# ict_v361-xs-180.net
KiCad netlist of a schematic drawn in EAGLE
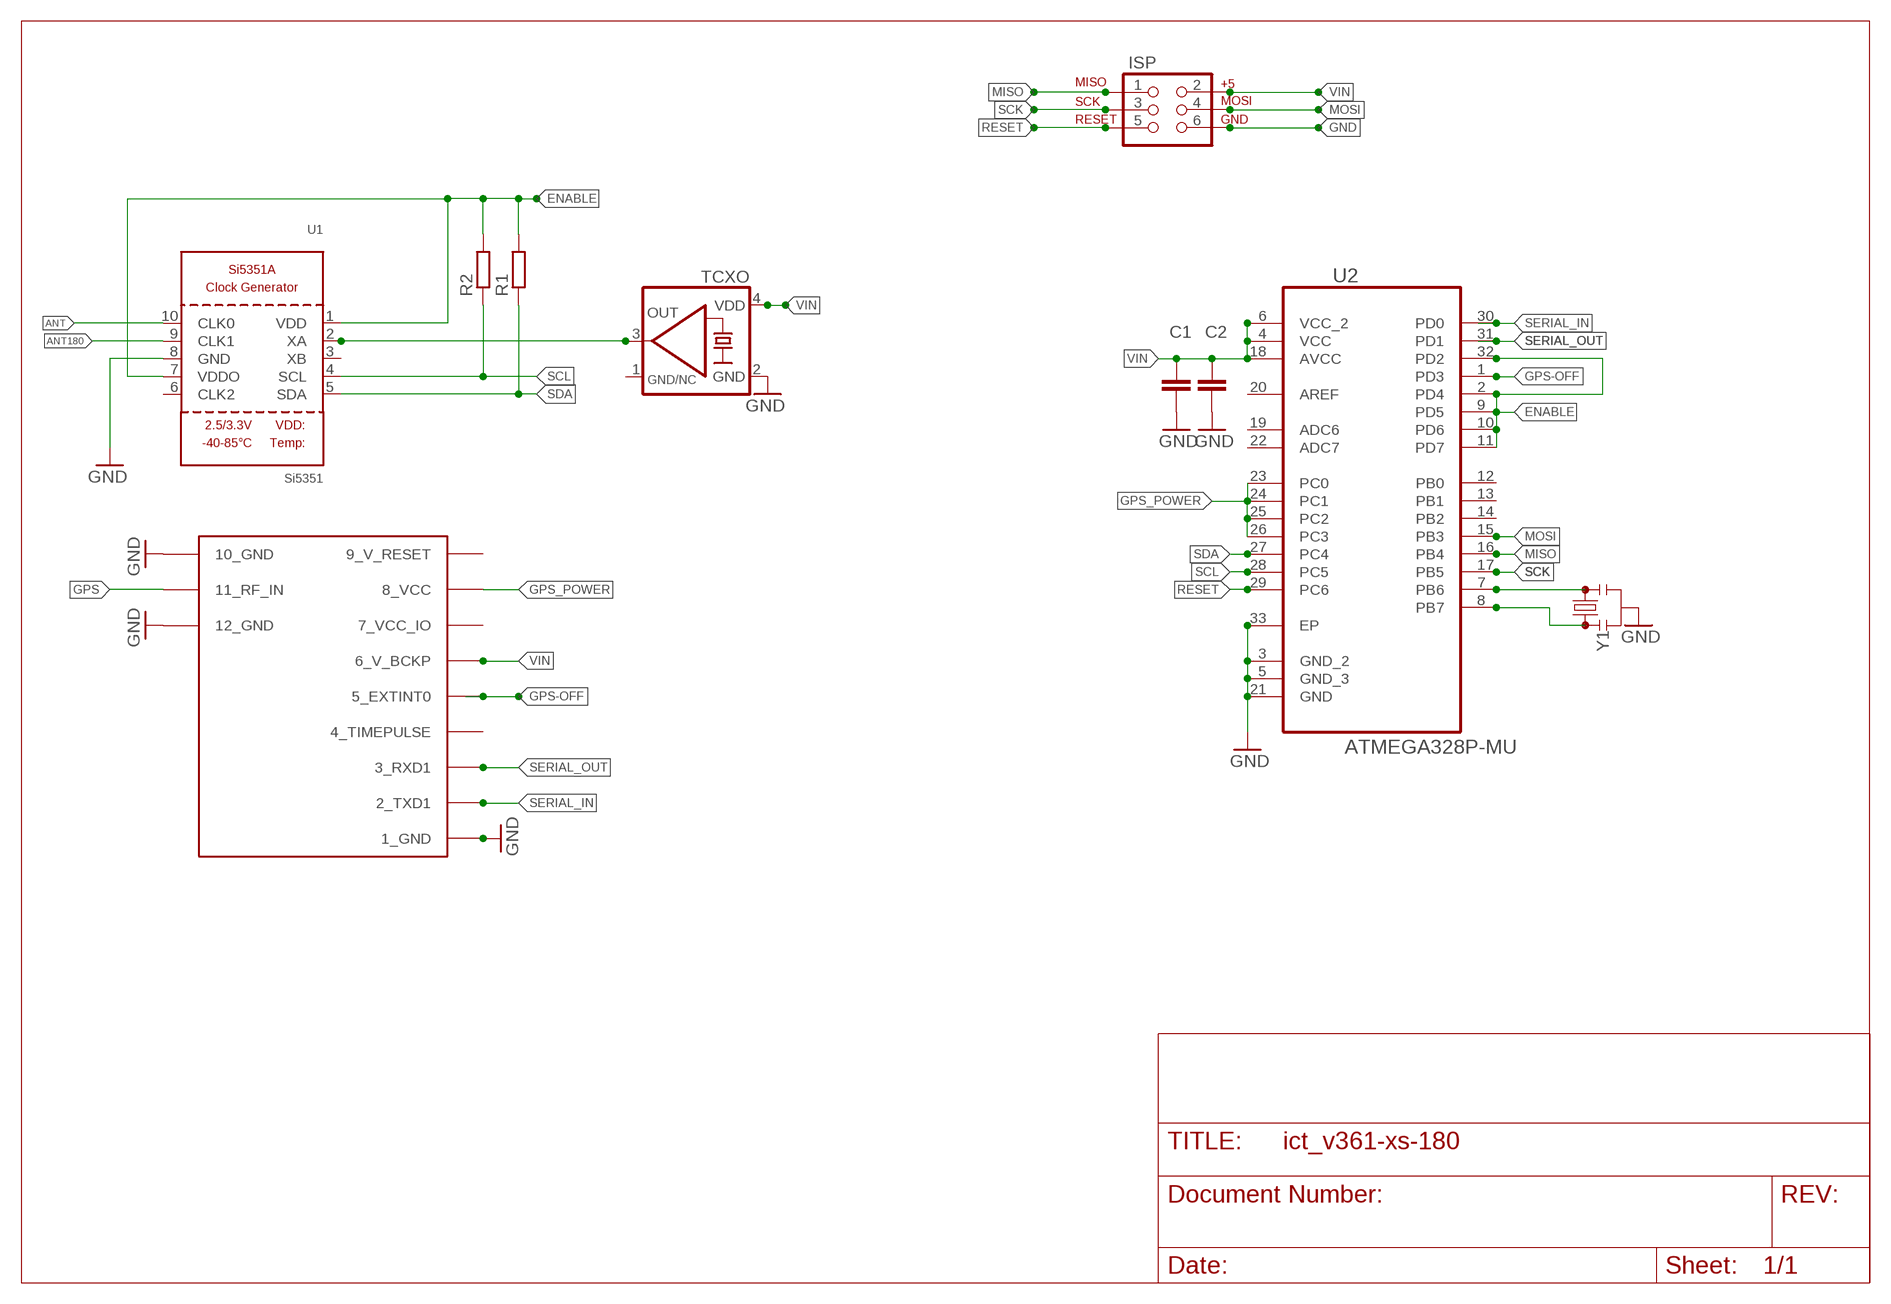
[diagram p0: schematic, sheet 1]

(export (version "E")
  (design (tool "Eeschema 10.0.6"))
  (components
    (comp (ref "C1")
      (value "C-EUC0603K")
      (footprint "eagle-import:C0603K")
      (libsource (lib "eagle-import") (part "C-EUC0603K"))
    )
    (comp (ref "C2")
      (value "C-EUC0603K")
      (footprint "eagle-import:C0603K")
      (libsource (lib "eagle-import") (part "C-EUC0603K"))
    )
    (comp (ref "GPS")
      (value "UBLOX_MAX")
      (footprint "eagle-import:UBLOX_MAX")
      (libsource (lib "eagle-import") (part "UBLOX_MAX"))
    )
    (comp (ref "ISP")
      (value "AVR_SPI_PRG_6PTH")
      (footprint "eagle-import:2X3")
      (libsource (lib "eagle-import") (part "AVR_SPI_PRG_6PTH"))
    )
    (comp (ref "R1")
      (value "R-EU_R0603")
      (footprint "eagle-import:R0603")
      (libsource (lib "eagle-import") (part "R-EU_R0603"))
    )
    (comp (ref "R2")
      (value "R-EU_R0603")
      (footprint "eagle-import:R0603")
      (libsource (lib "eagle-import") (part "R-EU_R0603"))
    )
    (comp (ref "TCXO")
      (value "KXO-TCXO-CMOS-84")
      (footprint "eagle-import:3.2X2.5_KXO-84-TCXO")
      (libsource (lib "eagle-import") (part "KXO-TCXO-CMOS-84"))
    )
    (comp (ref "U1")
      (value "Si5351")
      (footprint "eagle-import:MSOP10")
      (libsource (lib "eagle-import") (part "SI5351A"))
    )
    (comp (ref "U2")
      (value "ATMEGA328P-MU")
      (footprint "eagle-import:QFN50P500X500X100-33N")
      (libsource (lib "eagle-import") (part "ATMEGA328P-MU"))
    )
    (comp (ref "Y1")
      (value "RESONATORSMD-4.5X2.0")
      (footprint "eagle-import:RESONATOR-SMD-4.5X2.0")
      (libsource (lib "eagle-import") (part "RESONATORSMD-4.5X2.0"))
    )
  )
  (nets
    (net (code "1") (name "/7_VCC_IO") (class "Default")
      (node (ref "GPS") (pin "7_VCC_IO") (pinfunction "7_VCC_IO_7_VCC_IO") (pintype "power_in"))
    )
    (net (code "2") (name "/9_V_RESET") (class "Default")
      (node (ref "GPS") (pin "9_V_RESET") (pinfunction "9_V_RESET_9_V_RESET") (pintype "power_in"))
    )
    (net (code "3") (name "/GND{slash}NC") (class "Default")
      (node (ref "TCXO") (pin "1") (pinfunction "GND/NC_1") (pintype "power_in"))
    )
    (net (code "4") (name "ANT") (class "Default")
      (node (ref "U1") (pin "10") (pinfunction "CLK0_10") (pintype "output"))
    )
    (net (code "5") (name "ANT180") (class "Default")
      (node (ref "U1") (pin "9") (pinfunction "CLK1_9") (pintype "output"))
    )
    (net (code "6") (name "ENABLE") (class "Default")
      (node (ref "R1") (pin "2") (pinfunction "2_2") (pintype "passive"))
      (node (ref "R2") (pin "2") (pinfunction "2_2") (pintype "passive"))
      (node (ref "U1") (pin "1") (pinfunction "VDD_1") (pintype "power_in"))
      (node (ref "U1") (pin "7") (pinfunction "VDDO_7") (pintype "power_in"))
      (node (ref "U2") (pin "10") (pinfunction "PD6_10") (pintype "bidirectional"))
      (node (ref "U2") (pin "11") (pinfunction "PD7_11") (pintype "bidirectional"))
      (node (ref "U2") (pin "2") (pinfunction "PD4_2") (pintype "bidirectional"))
      (node (ref "U2") (pin "32") (pinfunction "PD2_32") (pintype "bidirectional"))
      (node (ref "U2") (pin "9") (pinfunction "PD5_9") (pintype "bidirectional"))
    )
    (net (code "7") (name "GND") (class "Default")
      (node (ref "C1") (pin "2") (pinfunction "2_2") (pintype "passive"))
      (node (ref "C2") (pin "2") (pinfunction "2_2") (pintype "passive"))
      (node (ref "GPS") (pin "10_GND") (pinfunction "10_GND_10_GND") (pintype "power_in"))
      (node (ref "GPS") (pin "12_GND") (pinfunction "12_GND_12_GND") (pintype "power_in"))
      (node (ref "GPS") (pin "1_GND") (pinfunction "1_GND_1_GND") (pintype "power_in"))
      (node (ref "ISP") (pin "6") (pinfunction "6_6") (pintype "passive"))
      (node (ref "TCXO") (pin "2") (pinfunction "GND_2") (pintype "power_in"))
      (node (ref "U1") (pin "8") (pinfunction "GND_8") (pintype "power_in"))
      (node (ref "U2") (pin "21") (pinfunction "GND_21") (pintype "passive"))
      (node (ref "U2") (pin "3") (pinfunction "GND_2_3") (pintype "passive"))
      (node (ref "U2") (pin "33") (pinfunction "EP_33") (pintype "passive"))
      (node (ref "U2") (pin "5") (pinfunction "GND_3_5") (pintype "passive"))
      (node (ref "Y1") (pin "2") (pinfunction "2_2") (pintype "passive"))
    )
    (net (code "8") (name "GPS") (class "Default")
      (node (ref "GPS") (pin "11_RF_IN") (pinfunction "11_RF_IN_11_RF_IN") (pintype "bidirectional"))
    )
    (net (code "9") (name "GPS-OFF") (class "Default")
      (node (ref "GPS") (pin "5_EXTINT0") (pinfunction "5_EXTINT0_5_EXTINT0") (pintype "bidirectional"))
      (node (ref "U2") (pin "1") (pinfunction "PD3_1") (pintype "bidirectional"))
    )
    (net (code "10") (name "GPS_POWER") (class "Default")
      (node (ref "GPS") (pin "8_VCC") (pinfunction "8_VCC_8_VCC") (pintype "power_in"))
      (node (ref "U2") (pin "23") (pinfunction "PC0_23") (pintype "bidirectional"))
      (node (ref "U2") (pin "24") (pinfunction "PC1_24") (pintype "bidirectional"))
      (node (ref "U2") (pin "25") (pinfunction "PC2_25") (pintype "bidirectional"))
      (node (ref "U2") (pin "26") (pinfunction "PC3_26") (pintype "bidirectional"))
    )
    (net (code "11") (name "MISO") (class "Default")
      (node (ref "ISP") (pin "1") (pinfunction "1_1") (pintype "passive"))
      (node (ref "U2") (pin "16") (pinfunction "PB4_16") (pintype "bidirectional"))
    )
    (net (code "12") (name "MOSI") (class "Default")
      (node (ref "ISP") (pin "4") (pinfunction "4_4") (pintype "passive"))
      (node (ref "U2") (pin "15") (pinfunction "PB3_15") (pintype "bidirectional"))
    )
    (net (code "13") (name "Net-(TCXO-OUT)") (class "Default")
      (node (ref "TCXO") (pin "3") (pinfunction "OUT_3") (pintype "output"))
      (node (ref "U1") (pin "2") (pinfunction "XA_2") (pintype "input"))
    )
    (net (code "14") (name "Net-(U2-PB6)") (class "Default")
      (node (ref "U2") (pin "7") (pinfunction "PB6_7") (pintype "bidirectional"))
      (node (ref "Y1") (pin "3") (pinfunction "3_3") (pintype "passive"))
    )
    (net (code "15") (name "Net-(U2-PB7)") (class "Default")
      (node (ref "U2") (pin "8") (pinfunction "PB7_8") (pintype "bidirectional"))
      (node (ref "Y1") (pin "1") (pinfunction "1_1") (pintype "passive"))
    )
    (net (code "16") (name "RESET") (class "Default")
      (node (ref "ISP") (pin "5") (pinfunction "5_5") (pintype "passive"))
      (node (ref "U2") (pin "29") (pinfunction "PC6_29") (pintype "bidirectional"))
    )
    (net (code "17") (name "SCK") (class "Default")
      (node (ref "ISP") (pin "3") (pinfunction "3_3") (pintype "passive"))
      (node (ref "U2") (pin "17") (pinfunction "PB5_17") (pintype "bidirectional"))
    )
    (net (code "18") (name "SCL") (class "Default")
      (node (ref "R2") (pin "1") (pinfunction "1_1") (pintype "passive"))
      (node (ref "U1") (pin "4") (pinfunction "SCL_4") (pintype "input"))
      (node (ref "U2") (pin "28") (pinfunction "PC5_28") (pintype "bidirectional"))
    )
    (net (code "19") (name "SDA") (class "Default")
      (node (ref "R1") (pin "1") (pinfunction "1_1") (pintype "passive"))
      (node (ref "U1") (pin "5") (pinfunction "SDA_5") (pintype "bidirectional"))
      (node (ref "U2") (pin "27") (pinfunction "PC4_27") (pintype "bidirectional"))
    )
    (net (code "20") (name "SERIAL_IN") (class "Default")
      (node (ref "GPS") (pin "2_TXD1") (pinfunction "2_TXD1_2_TXD1") (pintype "bidirectional"))
      (node (ref "U2") (pin "30") (pinfunction "PD0_30") (pintype "bidirectional"))
    )
    (net (code "21") (name "SERIAL_OUT") (class "Default")
      (node (ref "GPS") (pin "3_RXD1") (pinfunction "3_RXD1_3_RXD1") (pintype "bidirectional"))
      (node (ref "U2") (pin "31") (pinfunction "PD1_31") (pintype "bidirectional"))
    )
    (net (code "22") (name "VIN") (class "Default")
      (node (ref "C1") (pin "1") (pinfunction "1_1") (pintype "passive"))
      (node (ref "C2") (pin "1") (pinfunction "1_1") (pintype "passive"))
      (node (ref "GPS") (pin "6_V_BCKP") (pinfunction "6_V_BCKP_6_V_BCKP") (pintype "bidirectional"))
      (node (ref "ISP") (pin "2") (pinfunction "2_2") (pintype "passive"))
      (node (ref "TCXO") (pin "4") (pinfunction "VDD_4") (pintype "power_in"))
      (node (ref "U2") (pin "18") (pinfunction "AVCC_18") (pintype "power_in"))
      (node (ref "U2") (pin "4") (pinfunction "VCC_4") (pintype "power_in"))
      (node (ref "U2") (pin "6") (pinfunction "VCC_2_6") (pintype "power_in"))
    )
    (net (code "23") (name "unconnected-(GPS-Pad4_TIMEPULSE)") (class "Default")
      (node (ref "GPS") (pin "4_TIMEPULSE") (pinfunction "4_TIMEPULSE_4_TIMEPULSE") (pintype "bidirectional"))
    )
    (net (code "24") (name "unconnected-(U1-CLK2-Pad6)") (class "Default")
      (node (ref "U1") (pin "6") (pinfunction "CLK2_6") (pintype "output"))
    )
    (net (code "25") (name "unconnected-(U1-XB-Pad3)") (class "Default")
      (node (ref "U1") (pin "3") (pinfunction "XB_3") (pintype "input"))
    )
    (net (code "26") (name "unconnected-(U2-ADC6-Pad19)") (class "Default")
      (node (ref "U2") (pin "19") (pinfunction "ADC6_19") (pintype "input"))
    )
    (net (code "27") (name "unconnected-(U2-ADC7-Pad22)") (class "Default")
      (node (ref "U2") (pin "22") (pinfunction "ADC7_22") (pintype "input"))
    )
    (net (code "28") (name "unconnected-(U2-AREF-Pad20)") (class "Default")
      (node (ref "U2") (pin "20") (pinfunction "AREF_20") (pintype "input"))
    )
    (net (code "29") (name "unconnected-(U2-PB0-Pad12)") (class "Default")
      (node (ref "U2") (pin "12") (pinfunction "PB0_12") (pintype "bidirectional"))
    )
    (net (code "30") (name "unconnected-(U2-PB1-Pad13)") (class "Default")
      (node (ref "U2") (pin "13") (pinfunction "PB1_13") (pintype "bidirectional"))
    )
    (net (code "31") (name "unconnected-(U2-PB2-Pad14)") (class "Default")
      (node (ref "U2") (pin "14") (pinfunction "PB2_14") (pintype "bidirectional"))
    )
  )
)
